# Projet.net
KiCad netlist of a schematic drawn in EAGLE
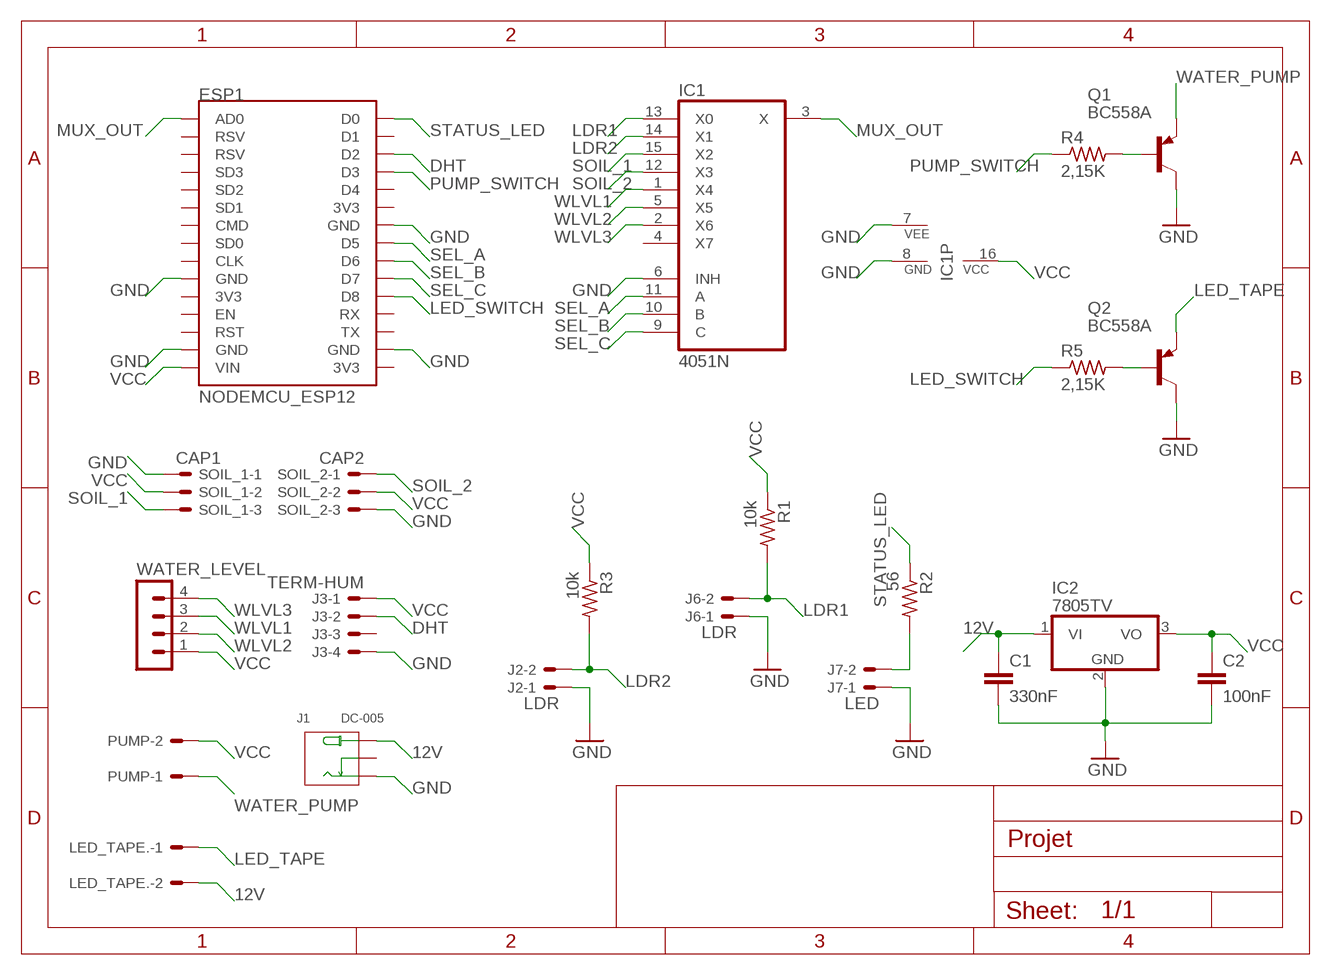
[diagram p0: schematic, sheet 1]

(export (version "E")
  (design (tool "Eeschema 10.0.6"))
  (components
    (comp (ref "C1")
      (value "330nF")
      (footprint "eagle-import:CAP_CERAMICO")
      (libsource (lib "eagle-import") (part "CAP_CERAMICO"))
    )
    (comp (ref "C2")
      (value "100nF")
      (footprint "eagle-import:CAP_CERAMICO")
      (libsource (lib "eagle-import") (part "CAP_CERAMICO"))
    )
    (comp (ref "ESP1")
      (value "NODEMCU_ESP12")
      (footprint "eagle-import:NODEMCU_ESP12")
      (libsource (lib "eagle-import") (part "NODEMCU_ESP12"))
    )
    (comp (ref "IC1")
      (value "4051N")
      (footprint "eagle-import:DIL16")
      (libsource (lib "eagle-import") (part "4051N"))
    )
    (comp (ref "IC2")
      (value "7805TV")
      (footprint "eagle-import:TO220V")
      (libsource (lib "eagle-import") (part "78TV05"))
    )
    (comp (ref "J1")
      (value "DC-005")
      (footprint "eagle-import:DCJ3P-14.2X11.0X9.0MM")
      (libsource (lib "eagle-import") (part "CONN-POWER-JACK-2.1MM(DC-005)"))
    )
    (comp (ref "J2")
      (value "LDR")
      (footprint "eagle-import:7395-02")
      (libsource (lib "eagle-import") (part "22-?-0205-7028"))
    )
    (comp (ref "J3")
      (value "TERM-HUM")
      (footprint "eagle-import:7395-04")
      (libsource (lib "eagle-import") (part "22-?-0405-7048"))
    )
    (comp (ref "J6")
      (value "LDR")
      (footprint "eagle-import:7395-02")
      (libsource (lib "eagle-import") (part "22-?-0205-7028"))
    )
    (comp (ref "J7")
      (value "LED")
      (footprint "eagle-import:7395-02")
      (libsource (lib "eagle-import") (part "22-?-0205-7028"))
    )
    (comp (ref "LED_TAPE.")
      (value "KK-156-2")
      (footprint "eagle-import:KK-156-2")
      (libsource (lib "eagle-import") (part "KK-156-2"))
    )
    (comp (ref "PUMP")
      (value "KK-156-2")
      (footprint "eagle-import:KK-156-2")
      (libsource (lib "eagle-import") (part "KK-156-2"))
    )
    (comp (ref "Q1")
      (value "BC558A")
      (footprint "eagle-import:TO92-EBC")
      (libsource (lib "eagle-import") (part "BC558A"))
    )
    (comp (ref "Q2")
      (value "BC558A")
      (footprint "eagle-import:TO92-EBC")
      (libsource (lib "eagle-import") (part "BC558A"))
    )
    (comp (ref "R1")
      (value "10k")
      (footprint "eagle-import:0204_7")
      (libsource (lib "eagle-import") (part "R-US_0204/7"))
    )
    (comp (ref "R2")
      (value "56")
      (footprint "eagle-import:0204_7")
      (libsource (lib "eagle-import") (part "R-US_0204/7"))
    )
    (comp (ref "R3")
      (value "10k")
      (footprint "eagle-import:0204_7")
      (libsource (lib "eagle-import") (part "R-US_0204/7"))
    )
    (comp (ref "R4")
      (value "2,15K")
      (footprint "eagle-import:0204_7")
      (libsource (lib "eagle-import") (part "R-US_0204/7"))
    )
    (comp (ref "R5")
      (value "2,15K")
      (footprint "eagle-import:0204_7")
      (libsource (lib "eagle-import") (part "R-US_0204/7"))
    )
    (comp (ref "SOIL_1")
      (value "CAP1")
      (footprint "eagle-import:7395-03")
      (libsource (lib "eagle-import") (part "22-?-0305-7038"))
    )
    (comp (ref "SOIL_2")
      (value "CAP2")
      (footprint "eagle-import:7395-03")
      (libsource (lib "eagle-import") (part "22-?-0305-7038"))
    )
    (comp (ref "WATER_LEVEL")
      (value "MA04-1")
      (footprint "eagle-import:MA04-1")
      (libsource (lib "eagle-import") (part "MA04-1"))
    )
  )
  (nets
    (net (code "1") (name "/12V") (class "Default")
      (node (ref "C1") (pin "P$1") (pinfunction "1_P$1") (pintype "passive"))
      (node (ref "IC2") (pin "1") (pinfunction "VI_1") (pintype "input"))
      (node (ref "J1") (pin "+") (pinfunction "+_+") (pintype "bidirectional"))
      (node (ref "LED_TAPE.") (pin "2") (pinfunction "S_2") (pintype "passive"))
    )
    (net (code "2") (name "/DHT") (class "Default")
      (node (ref "ESP1") (pin "D2") (pinfunction "D2_D2") (pintype "bidirectional"))
      (node (ref "J3") (pin "2") (pinfunction "S_2") (pintype "passive"))
    )
    (net (code "3") (name "/LDR1") (class "Default")
      (node (ref "IC1") (pin "13") (pinfunction "X0_13") (pintype "bidirectional"))
      (node (ref "J6") (pin "2") (pinfunction "S_2") (pintype "passive"))
      (node (ref "R1") (pin "2") (pinfunction "2_2") (pintype "passive"))
    )
    (net (code "4") (name "/LDR2") (class "Default")
      (node (ref "IC1") (pin "14") (pinfunction "X1_14") (pintype "bidirectional"))
      (node (ref "J2") (pin "2") (pinfunction "S_2") (pintype "passive"))
      (node (ref "R3") (pin "2") (pinfunction "2_2") (pintype "passive"))
    )
    (net (code "5") (name "/LED_SWITCH") (class "Default")
      (node (ref "ESP1") (pin "D8") (pinfunction "D8_D8") (pintype "bidirectional"))
      (node (ref "R5") (pin "1") (pinfunction "1_1") (pintype "passive"))
    )
    (net (code "6") (name "/LED_TAPE") (class "Default")
      (node (ref "LED_TAPE.") (pin "1") (pinfunction "S_1") (pintype "passive"))
      (node (ref "Q2") (pin "E") (pinfunction "E_E") (pintype "passive"))
    )
    (net (code "7") (name "/MUX_OUT") (class "Default")
      (node (ref "ESP1") (pin "AD0") (pinfunction "AD0_AD0") (pintype "bidirectional"))
      (node (ref "IC1") (pin "3") (pinfunction "X_3") (pintype "bidirectional"))
    )
    (net (code "8") (name "/PUMP_SWITCH") (class "Default")
      (node (ref "ESP1") (pin "D3") (pinfunction "D3_D3") (pintype "bidirectional"))
      (node (ref "R4") (pin "1") (pinfunction "1_1") (pintype "passive"))
    )
    (net (code "9") (name "/SEL_A") (class "Default")
      (node (ref "ESP1") (pin "D5") (pinfunction "D5_D5") (pintype "bidirectional"))
      (node (ref "IC1") (pin "11") (pinfunction "A_11") (pintype "input"))
    )
    (net (code "10") (name "/SEL_B") (class "Default")
      (node (ref "ESP1") (pin "D6") (pinfunction "D6_D6") (pintype "bidirectional"))
      (node (ref "IC1") (pin "10") (pinfunction "B_10") (pintype "input"))
    )
    (net (code "11") (name "/SEL_C") (class "Default")
      (node (ref "ESP1") (pin "D7") (pinfunction "D7_D7") (pintype "bidirectional"))
      (node (ref "IC1") (pin "9") (pinfunction "C_9") (pintype "input"))
    )
    (net (code "12") (name "/SOIL_1") (class "Default")
      (node (ref "IC1") (pin "15") (pinfunction "X2_15") (pintype "bidirectional"))
      (node (ref "SOIL_1") (pin "3") (pinfunction "S_3") (pintype "passive"))
    )
    (net (code "13") (name "/SOIL_2") (class "Default")
      (node (ref "IC1") (pin "12") (pinfunction "X3_12") (pintype "bidirectional"))
      (node (ref "SOIL_2") (pin "1") (pinfunction "S_1") (pintype "passive"))
    )
    (net (code "14") (name "/STATUS_LED") (class "Default")
      (node (ref "ESP1") (pin "D0") (pinfunction "D0_D0") (pintype "bidirectional"))
      (node (ref "R2") (pin "1") (pinfunction "1_1") (pintype "passive"))
    )
    (net (code "15") (name "/VCC") (class "Default")
      (node (ref "C2") (pin "P$1") (pinfunction "1_P$1") (pintype "passive"))
      (node (ref "ESP1") (pin "VIN") (pinfunction "VIN_VIN") (pintype "bidirectional"))
      (node (ref "IC1") (pin "16") (pinfunction "VCC_16") (pintype "power_in"))
      (node (ref "IC2") (pin "3") (pinfunction "VO_3") (pintype "passive"))
      (node (ref "J3") (pin "1") (pinfunction "S_1") (pintype "passive"))
      (node (ref "PUMP") (pin "2") (pinfunction "S_2") (pintype "passive"))
      (node (ref "R1") (pin "1") (pinfunction "1_1") (pintype "passive"))
      (node (ref "R3") (pin "1") (pinfunction "1_1") (pintype "passive"))
      (node (ref "SOIL_1") (pin "2") (pinfunction "S_2") (pintype "passive"))
      (node (ref "SOIL_2") (pin "2") (pinfunction "S_2") (pintype "passive"))
      (node (ref "WATER_LEVEL") (pin "1") (pinfunction "1_1") (pintype "passive"))
    )
    (net (code "16") (name "/WATER_PUMP") (class "Default")
      (node (ref "PUMP") (pin "1") (pinfunction "S_1") (pintype "passive"))
      (node (ref "Q1") (pin "E") (pinfunction "E_E") (pintype "passive"))
    )
    (net (code "17") (name "/WLVL1") (class "Default")
      (node (ref "IC1") (pin "1") (pinfunction "X4_1") (pintype "bidirectional"))
      (node (ref "WATER_LEVEL") (pin "3") (pinfunction "3_3") (pintype "passive"))
    )
    (net (code "18") (name "/WLVL2") (class "Default")
      (node (ref "IC1") (pin "5") (pinfunction "X5_5") (pintype "bidirectional"))
      (node (ref "WATER_LEVEL") (pin "2") (pinfunction "2_2") (pintype "passive"))
    )
    (net (code "19") (name "/WLVL3") (class "Default")
      (node (ref "IC1") (pin "2") (pinfunction "X6_2") (pintype "bidirectional"))
      (node (ref "WATER_LEVEL") (pin "4") (pinfunction "4_4") (pintype "passive"))
    )
    (net (code "20") (name "GND") (class "Default")
      (node (ref "C1") (pin "P$2") (pinfunction "2_P$2") (pintype "passive"))
      (node (ref "C2") (pin "P$2") (pinfunction "2_P$2") (pintype "passive"))
      (node (ref "ESP1") (pin "GND@0") (pinfunction "GND_GND@0") (pintype "bidirectional"))
      (node (ref "ESP1") (pin "GND@1") (pinfunction "GND_GND@1") (pintype "bidirectional"))
      (node (ref "ESP1") (pin "GND@2") (pinfunction "GND_GND@2") (pintype "bidirectional"))
      (node (ref "ESP1") (pin "GND@3") (pinfunction "GND_GND@3") (pintype "bidirectional"))
      (node (ref "IC1") (pin "6") (pinfunction "INH_6") (pintype "input"))
      (node (ref "IC1") (pin "7") (pinfunction "VEE_7") (pintype "power_in"))
      (node (ref "IC1") (pin "8") (pinfunction "GND_8") (pintype "power_in"))
      (node (ref "IC2") (pin "2") (pinfunction "GND_2") (pintype "passive"))
      (node (ref "J1") (pin "-1") (pinfunction "-_-1") (pintype "bidirectional"))
      (node (ref "J2") (pin "1") (pinfunction "S_1") (pintype "passive"))
      (node (ref "J3") (pin "4") (pinfunction "S_4") (pintype "passive"))
      (node (ref "J6") (pin "1") (pinfunction "S_1") (pintype "passive"))
      (node (ref "J7") (pin "1") (pinfunction "S_1") (pintype "passive"))
      (node (ref "Q1") (pin "C") (pinfunction "C_C") (pintype "passive"))
      (node (ref "Q2") (pin "C") (pinfunction "C_C") (pintype "passive"))
      (node (ref "SOIL_1") (pin "1") (pinfunction "S_1") (pintype "passive"))
      (node (ref "SOIL_2") (pin "3") (pinfunction "S_3") (pintype "passive"))
    )
    (net (code "21") (name "Net-(J7B-S)") (class "Default")
      (node (ref "J7") (pin "2") (pinfunction "S_2") (pintype "passive"))
      (node (ref "R2") (pin "2") (pinfunction "2_2") (pintype "passive"))
    )
    (net (code "22") (name "Net-(Q1-PadB)") (class "Default")
      (node (ref "Q1") (pin "B") (pinfunction "B_B") (pintype "passive"))
      (node (ref "R4") (pin "2") (pinfunction "2_2") (pintype "passive"))
    )
    (net (code "23") (name "Net-(Q2-PadB)") (class "Default")
      (node (ref "Q2") (pin "B") (pinfunction "B_B") (pintype "passive"))
      (node (ref "R5") (pin "2") (pinfunction "2_2") (pintype "passive"))
    )
    (net (code "24") (name "unconnected-(ESP1-3V3-Pad3V3@0)") (class "Default")
      (node (ref "ESP1") (pin "3V3@0") (pinfunction "3V3_3V3@0") (pintype "bidirectional"))
    )
    (net (code "25") (name "unconnected-(ESP1-3V3-Pad3V3@1)") (class "Default")
      (node (ref "ESP1") (pin "3V3@1") (pinfunction "3V3_3V3@1") (pintype "bidirectional"))
    )
    (net (code "26") (name "unconnected-(ESP1-3V3-Pad3V3@2)") (class "Default")
      (node (ref "ESP1") (pin "3V3@2") (pinfunction "3V3_3V3@2") (pintype "bidirectional"))
    )
    (net (code "27") (name "unconnected-(ESP1-PadCLK)") (class "Default")
      (node (ref "ESP1") (pin "CLK") (pinfunction "CLK_CLK") (pintype "bidirectional"))
    )
    (net (code "28") (name "unconnected-(ESP1-PadCMD)") (class "Default")
      (node (ref "ESP1") (pin "CMD") (pinfunction "CMD_CMD") (pintype "bidirectional"))
    )
    (net (code "29") (name "unconnected-(ESP1-PadD1)") (class "Default")
      (node (ref "ESP1") (pin "D1") (pinfunction "D1_D1") (pintype "bidirectional"))
    )
    (net (code "30") (name "unconnected-(ESP1-PadD4)") (class "Default")
      (node (ref "ESP1") (pin "D4") (pinfunction "D4_D4") (pintype "bidirectional"))
    )
    (net (code "31") (name "unconnected-(ESP1-PadEN)") (class "Default")
      (node (ref "ESP1") (pin "EN") (pinfunction "EN_EN") (pintype "bidirectional"))
    )
    (net (code "32") (name "unconnected-(ESP1-PadRST)") (class "Default")
      (node (ref "ESP1") (pin "RST") (pinfunction "RST_RST") (pintype "bidirectional"))
    )
    (net (code "33") (name "unconnected-(ESP1-PadRX)") (class "Default")
      (node (ref "ESP1") (pin "RX") (pinfunction "RX_RX") (pintype "bidirectional"))
    )
    (net (code "34") (name "unconnected-(ESP1-PadSD0)") (class "Default")
      (node (ref "ESP1") (pin "SD0") (pinfunction "SD0_SD0") (pintype "bidirectional"))
    )
    (net (code "35") (name "unconnected-(ESP1-PadSD1)") (class "Default")
      (node (ref "ESP1") (pin "SD1") (pinfunction "SD1_SD1") (pintype "bidirectional"))
    )
    (net (code "36") (name "unconnected-(ESP1-PadSD2)") (class "Default")
      (node (ref "ESP1") (pin "SD2") (pinfunction "SD2_SD2") (pintype "bidirectional"))
    )
    (net (code "37") (name "unconnected-(ESP1-PadSD3)") (class "Default")
      (node (ref "ESP1") (pin "SD3") (pinfunction "SD3_SD3") (pintype "bidirectional"))
    )
    (net (code "38") (name "unconnected-(ESP1-PadTX)") (class "Default")
      (node (ref "ESP1") (pin "TX") (pinfunction "TX_TX") (pintype "bidirectional"))
    )
    (net (code "39") (name "unconnected-(ESP1-RSV-PadRSV@0)") (class "Default")
      (node (ref "ESP1") (pin "RSV@0") (pinfunction "RSV_RSV@0") (pintype "bidirectional"))
    )
    (net (code "40") (name "unconnected-(ESP1-RSV-PadRSV@1)") (class "Default")
      (node (ref "ESP1") (pin "RSV@1") (pinfunction "RSV_RSV@1") (pintype "bidirectional"))
    )
    (net (code "41") (name "unconnected-(IC1A-X7-Pad4)") (class "Default")
      (node (ref "IC1") (pin "4") (pinfunction "X7_4") (pintype "bidirectional"))
    )
    (net (code "42") (name "unconnected-(J1-CDN-Pad-2)") (class "Default")
      (node (ref "J1") (pin "-2") (pinfunction "CDN_-2") (pintype "bidirectional"))
    )
    (net (code "43") (name "unconnected-(J3C-S-Pad3)") (class "Default")
      (node (ref "J3") (pin "3") (pinfunction "S_3") (pintype "passive"))
    )
  )
)
